# test.net
KiCad netlist of a schematic drawn in EAGLE
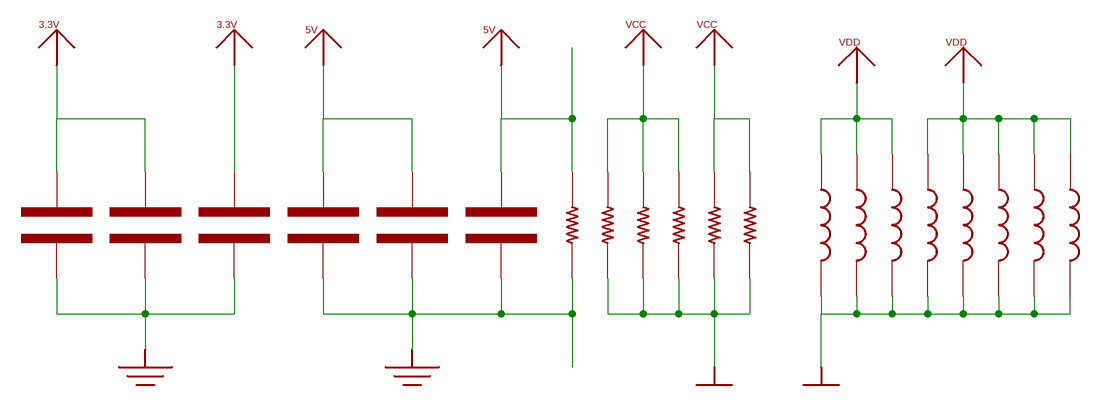
[diagram p0: schematic, sheet 1]

(export (version "E")
  (design (tool "Eeschema 10.0.6"))
  (components
    (comp (ref "C1")
      (value "CAP-0402")
      (footprint "eagle-import:0402-CAP")
      (libsource (lib "eagle-import") (part "CAP-0402"))
    )
    (comp (ref "C2")
      (value "CAP-0402")
      (footprint "eagle-import:0402-CAP")
      (libsource (lib "eagle-import") (part "CAP-0402"))
    )
    (comp (ref "C3")
      (value "CAP-0603")
      (footprint "eagle-import:0603-CAP")
      (libsource (lib "eagle-import") (part "CAP-0603"))
    )
    (comp (ref "C4")
      (value "CAP-0603")
      (footprint "eagle-import:0603-CAP")
      (libsource (lib "eagle-import") (part "CAP-0603"))
    )
    (comp (ref "C5")
      (value "CAP-0805")
      (footprint "eagle-import:0805")
      (libsource (lib "eagle-import") (part "CAP-0805"))
    )
    (comp (ref "C6")
      (value "CAP-0805")
      (footprint "eagle-import:0805")
      (libsource (lib "eagle-import") (part "CAP-0805"))
    )
    (comp (ref "L1")
      (value "IND-0402")
      (footprint "eagle-import:0402-CAP")
      (libsource (lib "eagle-import") (part "IND-0402"))
    )
    (comp (ref "L2")
      (value "IND-0402")
      (footprint "eagle-import:0402-CAP")
      (libsource (lib "eagle-import") (part "IND-0402"))
    )
    (comp (ref "L3")
      (value "IND-0603")
      (footprint "eagle-import:0603-CAP")
      (libsource (lib "eagle-import") (part "IND-0603"))
    )
    (comp (ref "L4")
      (value "IND-0603")
      (footprint "eagle-import:0603-CAP")
      (libsource (lib "eagle-import") (part "IND-0603"))
    )
    (comp (ref "L5")
      (value "IND-0805")
      (footprint "eagle-import:0805")
      (libsource (lib "eagle-import") (part "IND-0805"))
    )
    (comp (ref "L6")
      (value "IND-0805")
      (footprint "eagle-import:0805")
      (libsource (lib "eagle-import") (part "IND-0805"))
    )
    (comp (ref "L7")
      (value "IND-1206")
      (footprint "eagle-import:1206")
      (libsource (lib "eagle-import") (part "IND-1206"))
    )
    (comp (ref "L8")
      (value "IND-1206")
      (footprint "eagle-import:1206")
      (libsource (lib "eagle-import") (part "IND-1206"))
    )
    (comp (ref "R1")
      (value "RES-0402")
      (footprint "eagle-import:0402-RES")
      (libsource (lib "eagle-import") (part "RES-0402"))
    )
    (comp (ref "R2")
      (value "RES-0402")
      (footprint "eagle-import:0402-RES")
      (libsource (lib "eagle-import") (part "RES-0402"))
    )
    (comp (ref "R3")
      (value "RES-0603")
      (footprint "eagle-import:0603-RES")
      (libsource (lib "eagle-import") (part "RES-0603"))
    )
    (comp (ref "R4")
      (value "RES-0603")
      (footprint "eagle-import:0603-RES")
      (libsource (lib "eagle-import") (part "RES-0603"))
    )
    (comp (ref "R5")
      (value "RES-0805")
      (footprint "eagle-import:0805")
      (libsource (lib "eagle-import") (part "RES-0805"))
    )
    (comp (ref "R6")
      (value "RES-0805")
      (footprint "eagle-import:0805")
      (libsource (lib "eagle-import") (part "RES-0805"))
    )
  )
  (nets
    (net (code "1") (name "3.3V") (class "Default")
      (node (ref "C1") (pin "1") (pinfunction "1_1") (pintype "bidirectional"))
      (node (ref "C2") (pin "1") (pinfunction "1_1") (pintype "bidirectional"))
      (node (ref "C3") (pin "1") (pinfunction "1_1") (pintype "bidirectional"))
    )
    (net (code "2") (name "5V") (class "Default")
      (node (ref "C4") (pin "1") (pinfunction "1_1") (pintype "bidirectional"))
      (node (ref "C5") (pin "1") (pinfunction "1_1") (pintype "bidirectional"))
      (node (ref "C6") (pin "1") (pinfunction "1_1") (pintype "bidirectional"))
      (node (ref "R1") (pin "1") (pinfunction "1_1") (pintype "bidirectional"))
    )
    (net (code "3") (name "GND") (class "Default")
      (node (ref "C1") (pin "2") (pinfunction "2_2") (pintype "bidirectional"))
      (node (ref "C2") (pin "2") (pinfunction "2_2") (pintype "bidirectional"))
      (node (ref "C3") (pin "2") (pinfunction "2_2") (pintype "bidirectional"))
      (node (ref "C4") (pin "2") (pinfunction "2_2") (pintype "bidirectional"))
      (node (ref "C5") (pin "2") (pinfunction "2_2") (pintype "bidirectional"))
      (node (ref "C6") (pin "2") (pinfunction "2_2") (pintype "bidirectional"))
      (node (ref "R1") (pin "2") (pinfunction "2_2") (pintype "bidirectional"))
    )
    (net (code "4") (name "VCC") (class "Default")
      (node (ref "R2") (pin "1") (pinfunction "1_1") (pintype "bidirectional"))
      (node (ref "R3") (pin "1") (pinfunction "1_1") (pintype "bidirectional"))
      (node (ref "R4") (pin "1") (pinfunction "1_1") (pintype "bidirectional"))
      (node (ref "R5") (pin "1") (pinfunction "1_1") (pintype "bidirectional"))
      (node (ref "R6") (pin "1") (pinfunction "1_1") (pintype "bidirectional"))
    )
    (net (code "5") (name "VDD") (class "Default")
      (node (ref "L1") (pin "1") (pinfunction "1_1") (pintype "bidirectional"))
      (node (ref "L2") (pin "1") (pinfunction "1_1") (pintype "bidirectional"))
      (node (ref "L3") (pin "1") (pinfunction "1_1") (pintype "bidirectional"))
      (node (ref "L4") (pin "1") (pinfunction "1_1") (pintype "bidirectional"))
      (node (ref "L5") (pin "1") (pinfunction "1_1") (pintype "bidirectional"))
      (node (ref "L6") (pin "1") (pinfunction "1_1") (pintype "bidirectional"))
      (node (ref "L7") (pin "1") (pinfunction "1_1") (pintype "bidirectional"))
      (node (ref "L8") (pin "1") (pinfunction "1_1") (pintype "bidirectional"))
    )
    (net (code "6") (name "VSS") (class "Default")
      (node (ref "L1") (pin "2") (pinfunction "2_2") (pintype "bidirectional"))
      (node (ref "L2") (pin "2") (pinfunction "2_2") (pintype "bidirectional"))
      (node (ref "L3") (pin "2") (pinfunction "2_2") (pintype "bidirectional"))
      (node (ref "L4") (pin "2") (pinfunction "2_2") (pintype "bidirectional"))
      (node (ref "L5") (pin "2") (pinfunction "2_2") (pintype "bidirectional"))
      (node (ref "L6") (pin "2") (pinfunction "2_2") (pintype "bidirectional"))
      (node (ref "L7") (pin "2") (pinfunction "2_2") (pintype "bidirectional"))
      (node (ref "L8") (pin "2") (pinfunction "2_2") (pintype "bidirectional"))
      (node (ref "R2") (pin "2") (pinfunction "2_2") (pintype "bidirectional"))
      (node (ref "R3") (pin "2") (pinfunction "2_2") (pintype "bidirectional"))
      (node (ref "R4") (pin "2") (pinfunction "2_2") (pintype "bidirectional"))
      (node (ref "R5") (pin "2") (pinfunction "2_2") (pintype "bidirectional"))
      (node (ref "R6") (pin "2") (pinfunction "2_2") (pintype "bidirectional"))
    )
  )
)
